# ultra-violet-tooth-sensor-mk-1_2.net
KiCad netlist of a schematic drawn in EAGLE
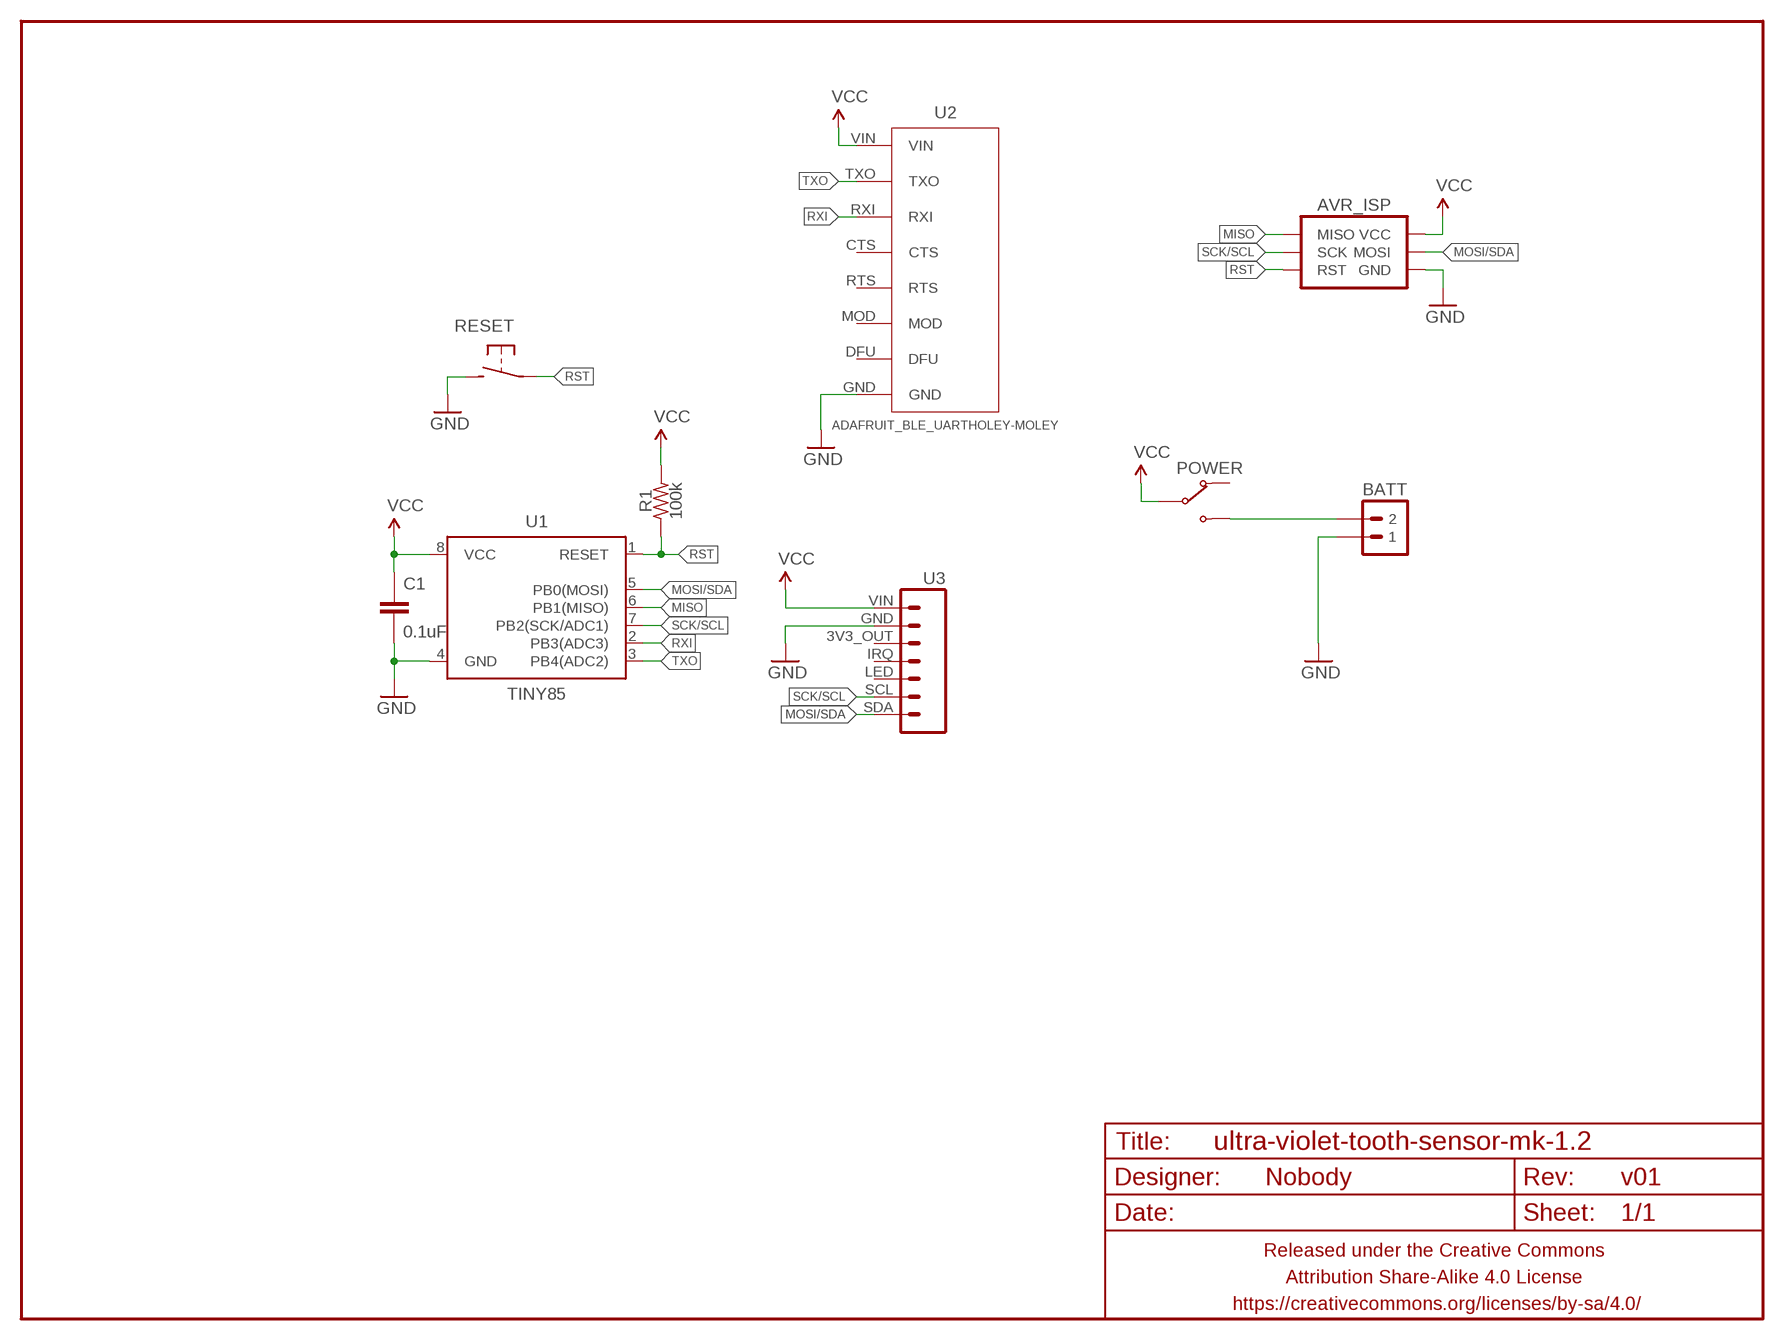
[diagram p0: schematic, sheet 1]

(export (version "E")
  (design (tool "Eeschema 10.0.6"))
  (components
    (comp (ref "AVR_ISP")
      (value "AVR_SPI_PRG_6PTH")
      (footprint "eagle-import:2X3")
      (libsource (lib "eagle-import") (part "AVR_SPI_PRG_6PTH"))
    )
    (comp (ref "BATT")
      (value "M02PTH-CENTERED-R+")
      (footprint "eagle-import:1X02-CENTER-R+")
      (libsource (lib "eagle-import") (part "M02PTH-CENTERED-R+"))
    )
    (comp (ref "C1")
      (value "0.1uF")
      (footprint "eagle-import:C025-024X044")
      (libsource (lib "eagle-import") (part "CAPACITOR-CERAMIC025-024X044"))
    )
    (comp (ref "FRAME1")
      (value "FRAME-LETTERNO_PACKAGE")
      (footprint "eagle-import:DUMMY")
      (fields (field (name "DESIGNER") "Nobody"))
      (libsource (lib "eagle-import") (part "FRAME-LETTERNO_PACKAGE"))
    )
    (comp (ref "POWER")
      (value "SWITCH-SPDTPTH-RA-2.54MM")
      (footprint "eagle-import:SPDT-RA-2.54MM")
      (libsource (lib "eagle-import") (part "SWITCH-SPDTPTH-RA-2.54MM"))
    )
    (comp (ref "R1")
      (value "100k")
      (footprint "eagle-import:RESISTOR-AXIAL-PTH-6.35MM")
      (libsource (lib "eagle-import") (part "RESISTORPTH-AXIAL-6.35MM"))
    )
    (comp (ref "RESET")
      (value "SPST-NO-TACT3MM-RA")
      (footprint "eagle-import:TACTILE-PTH-SIDE")
      (libsource (lib "eagle-import") (part "SPST-NO-TACT3MM-RA"))
    )
    (comp (ref "U1")
      (value "TINY85")
      (footprint "eagle-import:DIP08")
      (libsource (lib "eagle-import") (part "ATTINY45TINY85-20-DIP"))
    )
    (comp (ref "U2")
      (value "ADAFRUIT_BLE_UARTHOLEY-MOLEY")
      (footprint "eagle-import:ADAFRUIT_BLE_UART_HOLEY")
      (libsource (lib "eagle-import") (part "ADAFRUIT_BLE_UARTHOLEY-MOLEY"))
    )
    (comp (ref "U3")
      (value "ADAFRUIT-SI1145-BREAKOUT")
      (footprint "eagle-import:ADAFRUIT-SI1145-BREAKOUT")
      (libsource (lib "eagle-import") (part "ADAFRUIT-SI1145-BREAKOUT"))
    )
  )
  (nets
    (net (code "1") (name "GND") (class "Default")
      (node (ref "AVR_ISP") (pin "6") (pinfunction "GND_6") (pintype "passive"))
      (node (ref "BATT") (pin "1") (pinfunction "1_1") (pintype "passive"))
      (node (ref "C1") (pin "2") (pinfunction "2_2") (pintype "passive"))
      (node (ref "RESET") (pin "2") (pinfunction "2_2") (pintype "passive"))
      (node (ref "U1") (pin "4") (pinfunction "GND_4") (pintype "bidirectional"))
      (node (ref "U2") (pin "GND") (pinfunction "GND_GND") (pintype "bidirectional"))
      (node (ref "U3") (pin "GND") (pinfunction "GND_GND") (pintype "passive"))
    )
    (net (code "2") (name "MISO") (class "Default")
      (node (ref "AVR_ISP") (pin "1") (pinfunction "MISO_1") (pintype "passive"))
      (node (ref "U1") (pin "6") (pinfunction "PB1(MISO)_6") (pintype "bidirectional"))
    )
    (net (code "3") (name "MOSI{slash}SDA") (class "Default")
      (node (ref "AVR_ISP") (pin "4") (pinfunction "MOSI_4") (pintype "passive"))
      (node (ref "U1") (pin "5") (pinfunction "PB0(MOSI)_5") (pintype "bidirectional"))
      (node (ref "U3") (pin "SDA") (pinfunction "SDA_SDA") (pintype "passive"))
    )
    (net (code "4") (name "Net-(POWER-NO)") (class "Default")
      (node (ref "BATT") (pin "2") (pinfunction "2_2") (pintype "passive"))
      (node (ref "POWER") (pin "3") (pinfunction "NO_3") (pintype "passive"))
    )
    (net (code "5") (name "RST") (class "Default")
      (node (ref "AVR_ISP") (pin "5") (pinfunction "RST_5") (pintype "passive"))
      (node (ref "R1") (pin "P$1") (pinfunction "1_P$1") (pintype "passive"))
      (node (ref "RESET") (pin "1") (pinfunction "1_1") (pintype "passive"))
      (node (ref "U1") (pin "1") (pinfunction "RESET_1") (pintype "bidirectional"))
    )
    (net (code "6") (name "RXI") (class "Default")
      (node (ref "U1") (pin "2") (pinfunction "PB3(ADC3)_2") (pintype "bidirectional"))
      (node (ref "U2") (pin "RXI") (pinfunction "RXI_RXI") (pintype "bidirectional"))
    )
    (net (code "7") (name "SCK{slash}SCL") (class "Default")
      (node (ref "AVR_ISP") (pin "3") (pinfunction "SCK_3") (pintype "passive"))
      (node (ref "U1") (pin "7") (pinfunction "PB2(SCK/ADC1)_7") (pintype "bidirectional"))
      (node (ref "U3") (pin "SCL") (pinfunction "SCL_SCL") (pintype "passive"))
    )
    (net (code "8") (name "TXO") (class "Default")
      (node (ref "U1") (pin "3") (pinfunction "PB4(ADC2)_3") (pintype "bidirectional"))
      (node (ref "U2") (pin "TXO") (pinfunction "TXO_TXO") (pintype "bidirectional"))
    )
    (net (code "9") (name "VCC") (class "Default")
      (node (ref "AVR_ISP") (pin "2") (pinfunction "VCC_2") (pintype "passive"))
      (node (ref "C1") (pin "1") (pinfunction "1_1") (pintype "passive"))
      (node (ref "POWER") (pin "2") (pinfunction "COM_2") (pintype "passive"))
      (node (ref "R1") (pin "P$2") (pinfunction "2_P$2") (pintype "passive"))
      (node (ref "U1") (pin "8") (pinfunction "VCC_8") (pintype "bidirectional"))
      (node (ref "U2") (pin "VIN") (pinfunction "VIN_VIN") (pintype "bidirectional"))
      (node (ref "U3") (pin "VIN") (pinfunction "VIN_VIN") (pintype "passive"))
    )
    (net (code "10") (name "unconnected-(POWER-NC-Pad1)") (class "Default")
      (node (ref "POWER") (pin "1") (pinfunction "NC_1") (pintype "passive"))
    )
    (net (code "11") (name "unconnected-(U2-PadCTS)") (class "Default")
      (node (ref "U2") (pin "CTS") (pinfunction "CTS_CTS") (pintype "bidirectional"))
    )
    (net (code "12") (name "unconnected-(U2-PadDFU)") (class "Default")
      (node (ref "U2") (pin "DFU") (pinfunction "DFU_DFU") (pintype "bidirectional"))
    )
    (net (code "13") (name "unconnected-(U2-PadMOD)") (class "Default")
      (node (ref "U2") (pin "MOD") (pinfunction "MOD_MOD") (pintype "bidirectional"))
    )
    (net (code "14") (name "unconnected-(U2-PadRTS)") (class "Default")
      (node (ref "U2") (pin "RTS") (pinfunction "RTS_RTS") (pintype "bidirectional"))
    )
    (net (code "15") (name "unconnected-(U3-Pad3V3_OUT)") (class "Default")
      (node (ref "U3") (pin "3V3_OUT") (pinfunction "3V3_OUT_3V3_OUT") (pintype "passive"))
    )
    (net (code "16") (name "unconnected-(U3-PadIRQ)") (class "Default")
      (node (ref "U3") (pin "IRQ") (pinfunction "IRQ_IRQ") (pintype "passive"))
    )
    (net (code "17") (name "unconnected-(U3-PadLED)") (class "Default")
      (node (ref "U3") (pin "LED") (pinfunction "LED_LED") (pintype "passive"))
    )
  )
)
